# UC-521.net
KiCad netlist of a schematic drawn in Altium Designer
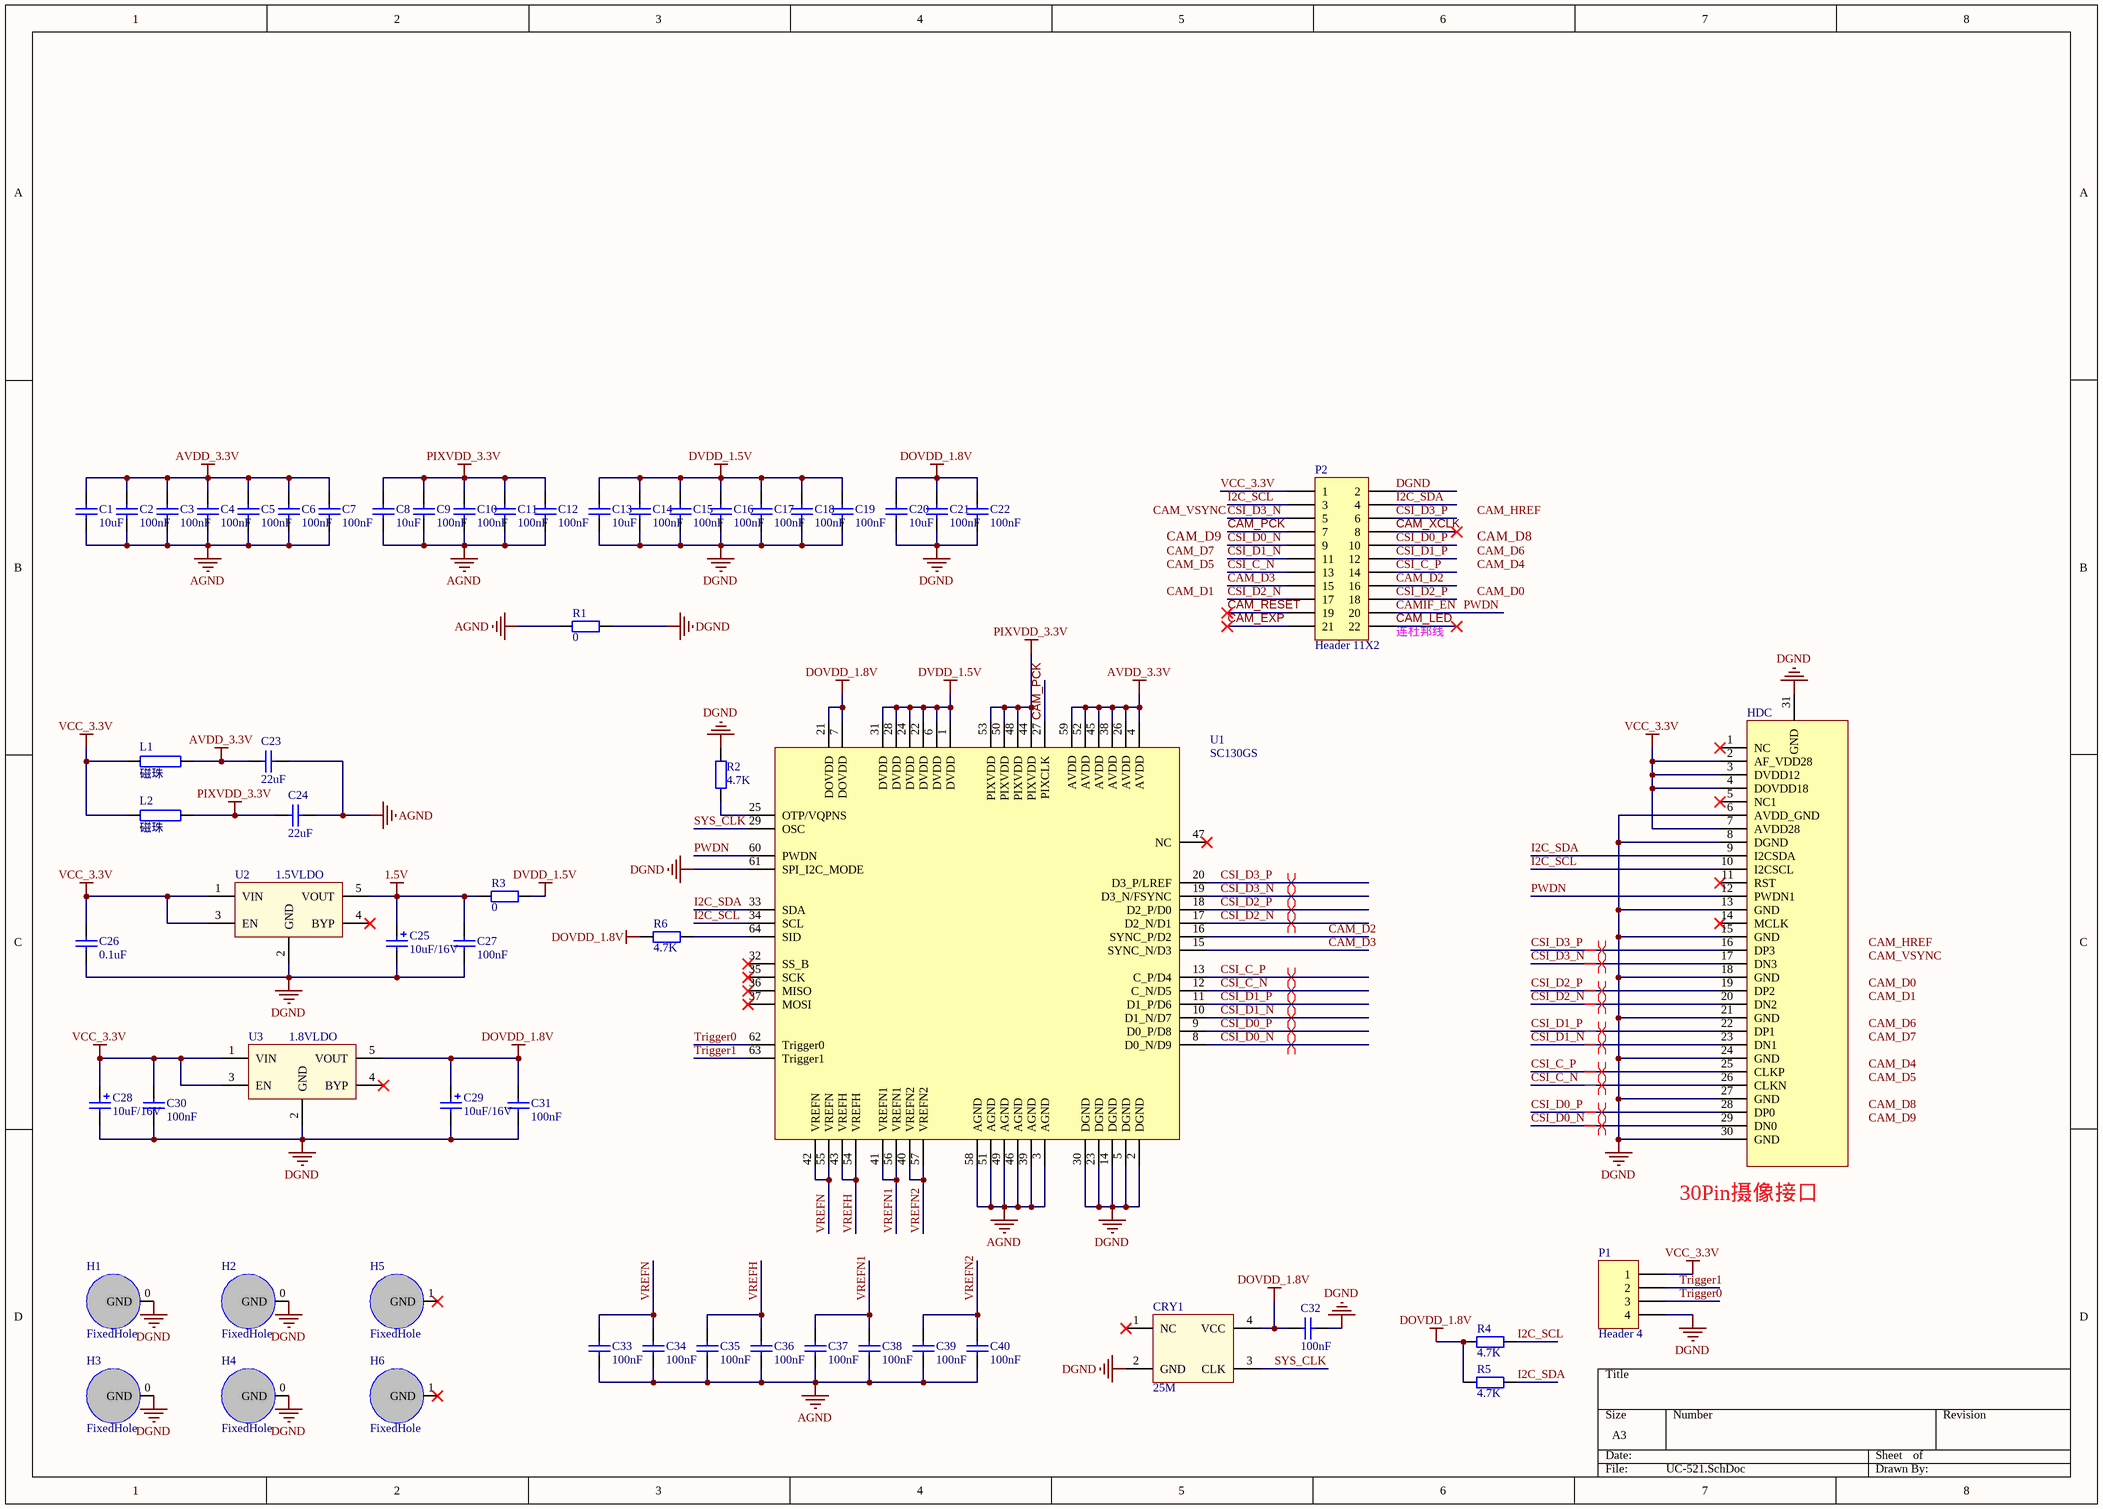
[diagram p0: UC-521.SchDoc]

(export (version "E")
  (design (tool "Eeschema 10.0.6"))
  (components
    (comp (ref "C1")
      (value "10uF")
      (footprint "C0603")
      (description "50V/8.2u/0805")
      (fields (field (name "PUBLISHER") "Altium Limited"))
      (libsource (lib "Miscellaneous Devices") (part "Cap"))
    )
    (comp (ref "C2")
      (value "100nF")
      (footprint "C0603")
      (description "50V/8.2u/0805")
      (fields (field (name "PUBLISHER") "Altium Limited"))
      (libsource (lib "Miscellaneous Devices") (part "Cap"))
    )
    (comp (ref "C3")
      (value "100nF")
      (footprint "C0603")
      (description "50V/8.2u/0805")
      (fields (field (name "PUBLISHER") "Altium Limited"))
      (libsource (lib "Miscellaneous Devices") (part "Cap"))
    )
    (comp (ref "C4")
      (value "100nF")
      (footprint "C0603")
      (description "50V/8.2u/0805")
      (fields (field (name "PUBLISHER") "Altium Limited"))
      (libsource (lib "Miscellaneous Devices") (part "Cap"))
    )
    (comp (ref "C5")
      (value "100nF")
      (footprint "C0603")
      (description "50V/8.2u/0805")
      (fields (field (name "PUBLISHER") "Altium Limited"))
      (libsource (lib "Miscellaneous Devices") (part "Cap"))
    )
    (comp (ref "C6")
      (value "100nF")
      (footprint "C0603")
      (description "50V/8.2u/0805")
      (fields (field (name "PUBLISHER") "Altium Limited"))
      (libsource (lib "Miscellaneous Devices") (part "Cap"))
    )
    (comp (ref "C7")
      (value "100nF")
      (footprint "C0603")
      (description "50V/8.2u/0805")
      (fields (field (name "PUBLISHER") "Altium Limited"))
      (libsource (lib "Miscellaneous Devices") (part "Cap"))
    )
    (comp (ref "C8")
      (value "10uF")
      (footprint "C0603")
      (description "50V/8.2u/0805")
      (fields (field (name "PUBLISHER") "Altium Limited"))
      (libsource (lib "Miscellaneous Devices") (part "Cap"))
    )
    (comp (ref "C9")
      (value "100nF")
      (footprint "C0603")
      (description "50V/8.2u/0805")
      (fields (field (name "PUBLISHER") "Altium Limited"))
      (libsource (lib "Miscellaneous Devices") (part "Cap"))
    )
    (comp (ref "C10")
      (value "100nF")
      (footprint "C0603")
      (description "50V/8.2u/0805")
      (fields (field (name "PUBLISHER") "Altium Limited"))
      (libsource (lib "Miscellaneous Devices") (part "Cap"))
    )
    (comp (ref "C11")
      (value "100nF")
      (footprint "C0603")
      (description "50V/8.2u/0805")
      (fields (field (name "PUBLISHER") "Altium Limited"))
      (libsource (lib "Miscellaneous Devices") (part "Cap"))
    )
    (comp (ref "C12")
      (value "100nF")
      (footprint "C0603")
      (description "50V/8.2u/0805")
      (fields (field (name "PUBLISHER") "Altium Limited"))
      (libsource (lib "Miscellaneous Devices") (part "Cap"))
    )
    (comp (ref "C13")
      (value "10uF")
      (footprint "C0603")
      (description "50V/8.2u/0805")
      (fields (field (name "PUBLISHER") "Altium Limited"))
      (libsource (lib "Miscellaneous Devices") (part "Cap"))
    )
    (comp (ref "C14")
      (value "100nF")
      (footprint "C0603")
      (description "50V/8.2u/0805")
      (fields (field (name "PUBLISHER") "Altium Limited"))
      (libsource (lib "Miscellaneous Devices") (part "Cap"))
    )
    (comp (ref "C15")
      (value "100nF")
      (footprint "C0603")
      (description "50V/8.2u/0805")
      (fields (field (name "PUBLISHER") "Altium Limited"))
      (libsource (lib "Miscellaneous Devices") (part "Cap"))
    )
    (comp (ref "C16")
      (value "100nF")
      (footprint "C0603")
      (description "50V/8.2u/0805")
      (fields (field (name "PUBLISHER") "Altium Limited"))
      (libsource (lib "Miscellaneous Devices") (part "Cap"))
    )
    (comp (ref "C17")
      (value "100nF")
      (footprint "C0603")
      (description "50V/8.2u/0805")
      (fields (field (name "PUBLISHER") "Altium Limited"))
      (libsource (lib "Miscellaneous Devices") (part "Cap"))
    )
    (comp (ref "C18")
      (value "100nF")
      (footprint "C0603")
      (description "50V/8.2u/0805")
      (fields (field (name "PUBLISHER") "Altium Limited"))
      (libsource (lib "Miscellaneous Devices") (part "Cap"))
    )
    (comp (ref "C19")
      (value "100nF")
      (footprint "C0603")
      (description "50V/8.2u/0805")
      (fields (field (name "PUBLISHER") "Altium Limited"))
      (libsource (lib "Miscellaneous Devices") (part "Cap"))
    )
    (comp (ref "C20")
      (value "10uF")
      (footprint "C0603")
      (description "50V/8.2u/0805")
      (fields (field (name "PUBLISHER") "Altium Limited"))
      (libsource (lib "Miscellaneous Devices") (part "Cap"))
    )
    (comp (ref "C21")
      (value "100nF")
      (footprint "C0603")
      (description "50V/8.2u/0805")
      (fields (field (name "PUBLISHER") "Altium Limited"))
      (libsource (lib "Miscellaneous Devices") (part "Cap"))
    )
    (comp (ref "C22")
      (value "100nF")
      (footprint "C0603")
      (description "50V/8.2u/0805")
      (fields (field (name "PUBLISHER") "Altium Limited"))
      (libsource (lib "Miscellaneous Devices") (part "Cap"))
    )
    (comp (ref "C23")
      (value "22uF")
      (footprint "C0603")
      (description "Capacitor")
      (fields (field (name "PUBLISHER") "Altium Limited"))
      (libsource (lib "Miscellaneous Devices") (part "Cap"))
    )
    (comp (ref "C24")
      (value "22uF")
      (footprint "C0603")
      (description "Capacitor")
      (fields (field (name "PUBLISHER") "Altium Limited"))
      (libsource (lib "Miscellaneous Devices") (part "Cap"))
    )
    (comp (ref "C25")
      (value "10uF/16V")
      (footprint "钽电容（A型）")
      (description "Polarized Capacitor (Axial)")
      (fields (field (name "PUBLISHER") "Altium Limited"))
      (libsource (lib "Miscellaneous Devices") (part "Cap Pol2"))
    )
    (comp (ref "C26")
      (value "0.1uF")
      (footprint "C0603")
      (description "Capacitor")
      (fields (field (name "PUBLISHER") "Altium Limited"))
      (libsource (lib "Miscellaneous Devices") (part "Cap"))
    )
    (comp (ref "C27")
      (value "100nF")
      (footprint "C0603")
      (description "Capacitor")
      (fields (field (name "PUBLISHER") "Altium Limited"))
      (libsource (lib "Miscellaneous Devices") (part "Cap"))
    )
    (comp (ref "C28")
      (value "10uF/16V")
      (footprint "钽电容（A型）")
      (description "Polarized Capacitor (Axial)")
      (fields (field (name "PUBLISHER") "Altium Limited"))
      (libsource (lib "Miscellaneous Devices") (part "Cap Pol2"))
    )
    (comp (ref "C29")
      (value "10uF/16V")
      (footprint "钽电容（A型）")
      (description "Polarized Capacitor (Axial)")
      (fields (field (name "PUBLISHER") "Altium Limited"))
      (libsource (lib "Miscellaneous Devices") (part "Cap Pol2"))
    )
    (comp (ref "C30")
      (value "100nF")
      (footprint "C0603")
      (description "Capacitor")
      (fields (field (name "PUBLISHER") "Altium Limited"))
      (libsource (lib "Miscellaneous Devices") (part "Cap"))
    )
    (comp (ref "C31")
      (value "100nF")
      (footprint "C0603")
      (description "Capacitor")
      (fields (field (name "PUBLISHER") "Altium Limited"))
      (libsource (lib "Miscellaneous Devices") (part "Cap"))
    )
    (comp (ref "C32")
      (value "100nF")
      (footprint "C0603")
      (description "50V/8.2u/0805")
      (fields (field (name "PUBLISHER") "Altium Limited"))
      (libsource (lib "Miscellaneous Devices") (part "Cap"))
    )
    (comp (ref "C33")
      (value "100nF")
      (footprint "C0603")
      (description "50V/8.2u/0805")
      (fields (field (name "PUBLISHER") "Altium Limited"))
      (libsource (lib "Miscellaneous Devices") (part "Cap"))
    )
    (comp (ref "C34")
      (value "100nF")
      (footprint "C0603")
      (description "50V/8.2u/0805")
      (fields (field (name "PUBLISHER") "Altium Limited"))
      (libsource (lib "Miscellaneous Devices") (part "Cap"))
    )
    (comp (ref "C35")
      (value "100nF")
      (footprint "C0603")
      (description "50V/8.2u/0805")
      (fields (field (name "PUBLISHER") "Altium Limited"))
      (libsource (lib "Miscellaneous Devices") (part "Cap"))
    )
    (comp (ref "C36")
      (value "100nF")
      (footprint "C0603")
      (description "50V/8.2u/0805")
      (fields (field (name "PUBLISHER") "Altium Limited"))
      (libsource (lib "Miscellaneous Devices") (part "Cap"))
    )
    (comp (ref "C37")
      (value "100nF")
      (footprint "C0603")
      (description "50V/8.2u/0805")
      (fields (field (name "PUBLISHER") "Altium Limited"))
      (libsource (lib "Miscellaneous Devices") (part "Cap"))
    )
    (comp (ref "C38")
      (value "100nF")
      (footprint "C0603")
      (description "50V/8.2u/0805")
      (fields (field (name "PUBLISHER") "Altium Limited"))
      (libsource (lib "Miscellaneous Devices") (part "Cap"))
    )
    (comp (ref "C39")
      (value "100nF")
      (footprint "C0603")
      (description "50V/8.2u/0805")
      (fields (field (name "PUBLISHER") "Altium Limited"))
      (libsource (lib "Miscellaneous Devices") (part "Cap"))
    )
    (comp (ref "C40")
      (value "100nF")
      (footprint "C0603")
      (description "50V/8.2u/0805")
      (fields (field (name "PUBLISHER") "Altium Limited"))
      (libsource (lib "Miscellaneous Devices") (part "Cap"))
    )
    (comp (ref "CRY1")
      (value "25M")
      (footprint "爱普生晶振3.2×2.5MM")
      (libsource (lib "MT9F002_V2.0") (part "24M"))
    )
    (comp (ref "H1")
      (value "FixedHole")
      (footprint "HOLE_M2")
      (libsource (lib "ITMS-02调试电缆转接板") (part "固定孔"))
    )
    (comp (ref "H2")
      (value "FixedHole")
      (footprint "HOLE_M2")
      (libsource (lib "ITMS-02调试电缆转接板") (part "固定孔"))
    )
    (comp (ref "H3")
      (value "FixedHole")
      (footprint "HOLE_M2")
      (libsource (lib "ITMS-02调试电缆转接板") (part "固定孔"))
    )
    (comp (ref "H4")
      (value "FixedHole")
      (footprint "HOLE_M2")
      (libsource (lib "ITMS-02调试电缆转接板") (part "固定孔"))
    )
    (comp (ref "H5") (value "FixedHole") (footprint "HOLE_M2") (libsource (lib "") (part "固定孔_1")))
    (comp (ref "H6") (value "FixedHole") (footprint "HOLE_M2") (libsource (lib "") (part "固定孔_1")))
    (comp (ref "HDC")
      (value "Component_1")
      (footprint "FH12-30S-0.5SH")
      (libsource (lib "Schlib1") (part "Component_1"))
    )
    (comp (ref "L1") (value "磁珠") (footprint "L0603") (libsource (lib "*") (part "RES")))
    (comp (ref "L2") (value "磁珠") (footprint "L0603") (libsource (lib "*") (part "RES")))
    (comp (ref "P1")
      (value "Header 4")
      (footprint "HDR1X4")
      (description "Header, 4-Pin")
      (fields (field (name "PUBLISHER") "Altium Limited"))
      (libsource (lib "Miscellaneous Connectors") (part "Header 4"))
    )
    (comp (ref "P2")
      (value "Header 11X2")
      (footprint "HDR2X11")
      (description "Header, 11-Pin, Dual row")
      (fields (field (name "PUBLISHER") "Altium Limited"))
      (libsource (lib "Miscellaneous Connectors") (part "Header 11X2"))
    )
    (comp (ref "R1")
      (value "0")
      (footprint "R0603")
      (description "Resistor")
      (fields (field (name "PUBLISHER") "Altium Limited"))
      (libsource (lib "DM642") (part "Res2"))
    )
    (comp (ref "R2")
      (value "4.7K")
      (footprint "R0603")
      (description "Resistor")
      (fields (field (name "PUBLISHER") "Altium Limited"))
      (libsource (lib "") (part "Res2_1"))
    )
    (comp (ref "R3")
      (value "0")
      (footprint "R0603")
      (description "Resistor")
      (fields (field (name "PUBLISHER") "Altium Limited"))
      (libsource (lib "DM642") (part "Res2"))
    )
    (comp (ref "R4")
      (value "4.7K")
      (footprint "R0603")
      (description "Resistor")
      (fields (field (name "PUBLISHER") "Altium Limited"))
      (libsource (lib "DM642") (part "Res2"))
    )
    (comp (ref "R5")
      (value "4.7K")
      (footprint "R0603")
      (description "Resistor")
      (fields (field (name "PUBLISHER") "Altium Limited"))
      (libsource (lib "DM642") (part "Res2"))
    )
    (comp (ref "R6")
      (value "4.7K")
      (footprint "R0603")
      (description "Resistor")
      (fields (field (name "PUBLISHER") "Altium Limited"))
      (libsource (lib "DM642") (part "Res2"))
    )
    (comp (ref "U1")
      (value "SC130GS")
      (footprint "LCC64-SC130GS")
      (libsource (lib "UC-5001") (part "SC130GS"))
    )
    (comp (ref "U2")
      (value "1.5VLDO")
      (footprint "SOT23-5")
      (libsource (lib "MT9F002_V2.0") (part "2.8VLDO"))
    )
    (comp (ref "U3")
      (value "1.8VLDO")
      (footprint "SOT23-5")
      (libsource (lib "MT9F002_V2.0") (part "2.8VLDO"))
    )
  )
  (nets
    (net (code "1") (name "/CAMIF_EN") (class "Default")
      (node (ref "HDC") (pin "12") (pinfunction "PWDN1_12") (pintype "passive"))
      (node (ref "P2") (pin "20") (pinfunction "20_20") (pintype "passive"))
      (node (ref "U1") (pin "60") (pinfunction "PWDN_60") (pintype "passive"))
    )
    (net (code "4") (name "/CAM_D2") (class "Default")
      (node (ref "P2") (pin "16") (pinfunction "16_16") (pintype "passive"))
      (node (ref "U1") (pin "16") (pinfunction "SYNC_P/D2_16") (pintype "passive"))
    )
    (net (code "5") (name "/CAM_D3") (class "Default")
      (node (ref "P2") (pin "15") (pinfunction "15_15") (pintype "passive"))
      (node (ref "U1") (pin "15") (pinfunction "SYNC_N/D3_15") (pintype "passive"))
    )
    (net (code "12") (name "/CAM_EXP") (class "Default")
      (node (ref "P2") (pin "21") (pinfunction "21_21") (pintype "passive+no_connect"))
    )
    (net (code "14") (name "/CAM_LED") (class "Default")
      (node (ref "P2") (pin "22") (pinfunction "22_22") (pintype "passive+no_connect"))
    )
    (net (code "15") (name "/CAM_PCK") (class "Default")
      (node (ref "P2") (pin "7") (pinfunction "7_7") (pintype "passive"))
      (node (ref "U1") (pin "27") (pinfunction "PIXCLK_27") (pintype "passive"))
    )
    (net (code "16") (name "/CAM_RESET") (class "Default")
      (node (ref "P2") (pin "19") (pinfunction "19_19") (pintype "passive+no_connect"))
    )
    (net (code "18") (name "/CAM_XCLK") (class "Default")
      (node (ref "P2") (pin "8") (pinfunction "8_8") (pintype "passive+no_connect"))
    )
    (net (code "19") (name "/CSI_C_N") (class "Default")
      (node (ref "HDC") (pin "26") (pinfunction "CLKN_26") (pintype "passive"))
      (node (ref "P2") (pin "13") (pinfunction "13_13") (pintype "passive"))
      (node (ref "U1") (pin "12") (pinfunction "C_N/D5_12") (pintype "passive"))
    )
    (net (code "20") (name "/CSI_C_P") (class "Default")
      (node (ref "HDC") (pin "25") (pinfunction "CLKP_25") (pintype "passive"))
      (node (ref "P2") (pin "14") (pinfunction "14_14") (pintype "passive"))
      (node (ref "U1") (pin "13") (pinfunction "C_P/D4_13") (pintype "passive"))
    )
    (net (code "21") (name "/CSI_D0_N") (class "Default")
      (node (ref "HDC") (pin "29") (pinfunction "DN0_29") (pintype "passive"))
      (node (ref "P2") (pin "9") (pinfunction "9_9") (pintype "passive"))
      (node (ref "U1") (pin "8") (pinfunction "D0_N/D9_8") (pintype "passive"))
    )
    (net (code "22") (name "/CSI_D0_P") (class "Default")
      (node (ref "HDC") (pin "28") (pinfunction "DP0_28") (pintype "passive"))
      (node (ref "P2") (pin "10") (pinfunction "10_10") (pintype "passive"))
      (node (ref "U1") (pin "9") (pinfunction "D0_P/D8_9") (pintype "passive"))
    )
    (net (code "23") (name "/CSI_D1_N") (class "Default")
      (node (ref "HDC") (pin "23") (pinfunction "DN1_23") (pintype "passive"))
      (node (ref "P2") (pin "11") (pinfunction "11_11") (pintype "passive"))
      (node (ref "U1") (pin "10") (pinfunction "D1_N/D7_10") (pintype "passive"))
    )
    (net (code "24") (name "/CSI_D1_P") (class "Default")
      (node (ref "HDC") (pin "22") (pinfunction "DP1_22") (pintype "passive"))
      (node (ref "P2") (pin "12") (pinfunction "12_12") (pintype "passive"))
      (node (ref "U1") (pin "11") (pinfunction "D1_P/D6_11") (pintype "passive"))
    )
    (net (code "25") (name "/CSI_D2_N") (class "Default")
      (node (ref "HDC") (pin "20") (pinfunction "DN2_20") (pintype "passive"))
      (node (ref "P2") (pin "17") (pinfunction "17_17") (pintype "passive"))
      (node (ref "U1") (pin "17") (pinfunction "D2_N/D1_17") (pintype "passive"))
    )
    (net (code "26") (name "/CSI_D2_P") (class "Default")
      (node (ref "HDC") (pin "19") (pinfunction "DP2_19") (pintype "passive"))
      (node (ref "P2") (pin "18") (pinfunction "18_18") (pintype "passive"))
      (node (ref "U1") (pin "18") (pinfunction "D2_P/D0_18") (pintype "passive"))
    )
    (net (code "27") (name "/CSI_D3_N") (class "Default")
      (node (ref "HDC") (pin "17") (pinfunction "DN3_17") (pintype "passive"))
      (node (ref "P2") (pin "5") (pinfunction "5_5") (pintype "passive"))
      (node (ref "U1") (pin "19") (pinfunction "D3_N/FSYNC_19") (pintype "passive"))
    )
    (net (code "28") (name "/CSI_D3_P") (class "Default")
      (node (ref "HDC") (pin "16") (pinfunction "DP3_16") (pintype "passive"))
      (node (ref "P2") (pin "6") (pinfunction "6_6") (pintype "passive"))
      (node (ref "U1") (pin "20") (pinfunction "D3_P/LREF_20") (pintype "passive"))
    )
    (net (code "29") (name "/I2C_SCL") (class "Default")
      (node (ref "HDC") (pin "10") (pinfunction "I2CSCL_10") (pintype "passive"))
      (node (ref "P2") (pin "3") (pinfunction "3_3") (pintype "passive"))
      (node (ref "R4") (pin "2") (pinfunction "2_2") (pintype "passive"))
      (node (ref "U1") (pin "34") (pinfunction "SCL_34") (pintype "passive"))
    )
    (net (code "30") (name "/I2C_SDA") (class "Default")
      (node (ref "HDC") (pin "9") (pinfunction "I2CSDA_9") (pintype "passive"))
      (node (ref "P2") (pin "4") (pinfunction "4_4") (pintype "passive"))
      (node (ref "R5") (pin "2") (pinfunction "2_2") (pintype "passive"))
      (node (ref "U1") (pin "33") (pinfunction "SDA_33") (pintype "passive"))
    )
    (net (code "31") (name "/SYS_CLK") (class "Default")
      (node (ref "CRY1") (pin "3") (pinfunction "CLK_3") (pintype "passive"))
      (node (ref "U1") (pin "29") (pinfunction "OSC_29") (pintype "passive"))
    )
    (net (code "32") (name "/Trigger0") (class "Default")
      (node (ref "P1") (pin "3") (pinfunction "3_3") (pintype "passive"))
      (node (ref "U1") (pin "62") (pinfunction "Trigger0_62") (pintype "passive"))
    )
    (net (code "33") (name "/Trigger1") (class "Default")
      (node (ref "P1") (pin "2") (pinfunction "2_2") (pintype "passive"))
      (node (ref "U1") (pin "63") (pinfunction "Trigger1_63") (pintype "passive"))
    )
    (net (code "34") (name "/VREFH") (class "Default")
      (node (ref "C35") (pin "1") (pinfunction "1_1") (pintype "passive"))
      (node (ref "C36") (pin "1") (pinfunction "1_1") (pintype "passive"))
      (node (ref "U1") (pin "43") (pinfunction "VREFH_43") (pintype "passive"))
      (node (ref "U1") (pin "54") (pinfunction "VREFH_54") (pintype "passive"))
    )
    (net (code "35") (name "/VREFN") (class "Default")
      (node (ref "C33") (pin "1") (pinfunction "1_1") (pintype "passive"))
      (node (ref "C34") (pin "1") (pinfunction "1_1") (pintype "passive"))
      (node (ref "U1") (pin "42") (pinfunction "VREFN_42") (pintype "passive"))
      (node (ref "U1") (pin "55") (pinfunction "VREFN_55") (pintype "passive"))
    )
    (net (code "36") (name "/VREFN1") (class "Default")
      (node (ref "C37") (pin "1") (pinfunction "1_1") (pintype "passive"))
      (node (ref "C38") (pin "1") (pinfunction "1_1") (pintype "passive"))
      (node (ref "U1") (pin "41") (pinfunction "VREFN1_41") (pintype "passive"))
      (node (ref "U1") (pin "56") (pinfunction "VREFN1_56") (pintype "passive"))
    )
    (net (code "37") (name "/VREFN2") (class "Default")
      (node (ref "C39") (pin "1") (pinfunction "1_1") (pintype "passive"))
      (node (ref "C40") (pin "1") (pinfunction "1_1") (pintype "passive"))
      (node (ref "U1") (pin "40") (pinfunction "VREFN2_40") (pintype "passive"))
      (node (ref "U1") (pin "57") (pinfunction "VREFN2_57") (pintype "passive"))
    )
    (net (code "38") (name "1.5V") (class "Default")
      (node (ref "C25") (pin "1") (pinfunction "1_1") (pintype "passive"))
      (node (ref "C27") (pin "1") (pinfunction "1_1") (pintype "passive"))
      (node (ref "R3") (pin "1") (pinfunction "1_1") (pintype "passive"))
      (node (ref "U2") (pin "5") (pinfunction "VOUT_5") (pintype "passive"))
    )
    (net (code "39") (name "AGND") (class "Default")
      (node (ref "C1") (pin "2") (pinfunction "2_2") (pintype "passive"))
      (node (ref "C10") (pin "2") (pinfunction "2_2") (pintype "passive"))
      (node (ref "C11") (pin "2") (pinfunction "2_2") (pintype "passive"))
      (node (ref "C12") (pin "2") (pinfunction "2_2") (pintype "passive"))
      (node (ref "C2") (pin "2") (pinfunction "2_2") (pintype "passive"))
      (node (ref "C23") (pin "1") (pinfunction "1_1") (pintype "passive"))
      (node (ref "C24") (pin "1") (pinfunction "1_1") (pintype "passive"))
      (node (ref "C3") (pin "2") (pinfunction "2_2") (pintype "passive"))
      (node (ref "C33") (pin "2") (pinfunction "2_2") (pintype "passive"))
      (node (ref "C34") (pin "2") (pinfunction "2_2") (pintype "passive"))
      (node (ref "C35") (pin "2") (pinfunction "2_2") (pintype "passive"))
      (node (ref "C36") (pin "2") (pinfunction "2_2") (pintype "passive"))
      (node (ref "C37") (pin "2") (pinfunction "2_2") (pintype "passive"))
      (node (ref "C38") (pin "2") (pinfunction "2_2") (pintype "passive"))
      (node (ref "C39") (pin "2") (pinfunction "2_2") (pintype "passive"))
      (node (ref "C4") (pin "2") (pinfunction "2_2") (pintype "passive"))
      (node (ref "C40") (pin "2") (pinfunction "2_2") (pintype "passive"))
      (node (ref "C5") (pin "2") (pinfunction "2_2") (pintype "passive"))
      (node (ref "C6") (pin "2") (pinfunction "2_2") (pintype "passive"))
      (node (ref "C7") (pin "2") (pinfunction "2_2") (pintype "passive"))
      (node (ref "C8") (pin "2") (pinfunction "2_2") (pintype "passive"))
      (node (ref "C9") (pin "2") (pinfunction "2_2") (pintype "passive"))
      (node (ref "R1") (pin "1") (pinfunction "1_1") (pintype "passive"))
      (node (ref "U1") (pin "3") (pinfunction "AGND_3") (pintype "passive"))
      (node (ref "U1") (pin "39") (pinfunction "AGND_39") (pintype "passive"))
      (node (ref "U1") (pin "46") (pinfunction "AGND_46") (pintype "passive"))
      (node (ref "U1") (pin "49") (pinfunction "AGND_49") (pintype "passive"))
      (node (ref "U1") (pin "51") (pinfunction "AGND_51") (pintype "passive"))
      (node (ref "U1") (pin "58") (pinfunction "AGND_58") (pintype "passive"))
    )
    (net (code "40") (name "AVDD_3.3V") (class "Default")
      (node (ref "C1") (pin "1") (pinfunction "1_1") (pintype "passive"))
      (node (ref "C2") (pin "1") (pinfunction "1_1") (pintype "passive"))
      (node (ref "C23") (pin "2") (pinfunction "2_2") (pintype "passive"))
      (node (ref "C3") (pin "1") (pinfunction "1_1") (pintype "passive"))
      (node (ref "C4") (pin "1") (pinfunction "1_1") (pintype "passive"))
      (node (ref "C5") (pin "1") (pinfunction "1_1") (pintype "passive"))
      (node (ref "C6") (pin "1") (pinfunction "1_1") (pintype "passive"))
      (node (ref "C7") (pin "1") (pinfunction "1_1") (pintype "passive"))
      (node (ref "L1") (pin "2") (pinfunction "2_2") (pintype "passive"))
      (node (ref "U1") (pin "26") (pinfunction "AVDD_26") (pintype "passive"))
      (node (ref "U1") (pin "38") (pinfunction "AVDD_38") (pintype "passive"))
      (node (ref "U1") (pin "4") (pinfunction "AVDD_4") (pintype "passive"))
      (node (ref "U1") (pin "45") (pinfunction "AVDD_45") (pintype "passive"))
      (node (ref "U1") (pin "52") (pinfunction "AVDD_52") (pintype "passive"))
      (node (ref "U1") (pin "59") (pinfunction "AVDD_59") (pintype "passive"))
    )
    (net (code "41") (name "DGND") (class "Default")
      (node (ref "C13") (pin "2") (pinfunction "2_2") (pintype "passive"))
      (node (ref "C14") (pin "2") (pinfunction "2_2") (pintype "passive"))
      (node (ref "C15") (pin "2") (pinfunction "2_2") (pintype "passive"))
      (node (ref "C16") (pin "2") (pinfunction "2_2") (pintype "passive"))
      (node (ref "C17") (pin "2") (pinfunction "2_2") (pintype "passive"))
      (node (ref "C18") (pin "2") (pinfunction "2_2") (pintype "passive"))
      (node (ref "C19") (pin "2") (pinfunction "2_2") (pintype "passive"))
      (node (ref "C20") (pin "2") (pinfunction "2_2") (pintype "passive"))
      (node (ref "C21") (pin "2") (pinfunction "2_2") (pintype "passive"))
      (node (ref "C22") (pin "2") (pinfunction "2_2") (pintype "passive"))
      (node (ref "C25") (pin "2") (pinfunction "2_2") (pintype "passive"))
      (node (ref "C26") (pin "2") (pinfunction "2_2") (pintype "passive"))
      (node (ref "C27") (pin "2") (pinfunction "2_2") (pintype "passive"))
      (node (ref "C28") (pin "2") (pinfunction "2_2") (pintype "passive"))
      (node (ref "C29") (pin "2") (pinfunction "2_2") (pintype "passive"))
      (node (ref "C30") (pin "2") (pinfunction "2_2") (pintype "passive"))
      (node (ref "C31") (pin "2") (pinfunction "2_2") (pintype "passive"))
      (node (ref "C32") (pin "2") (pinfunction "2_2") (pintype "passive"))
      (node (ref "CRY1") (pin "2") (pinfunction "GND_2") (pintype "passive"))
      (node (ref "H1") (pin "0") (pinfunction "GND_0") (pintype "passive"))
      (node (ref "H2") (pin "0") (pinfunction "GND_0") (pintype "passive"))
      (node (ref "H3") (pin "0") (pinfunction "GND_0") (pintype "passive"))
      (node (ref "H4") (pin "0") (pinfunction "GND_0") (pintype "passive"))
      (node (ref "HDC") (pin "13") (pinfunction "GND_13") (pintype "passive"))
      (node (ref "HDC") (pin "15") (pinfunction "GND_15") (pintype "passive"))
      (node (ref "HDC") (pin "18") (pinfunction "GND_18") (pintype "passive"))
      (node (ref "HDC") (pin "21") (pinfunction "GND_21") (pintype "passive"))
      (node (ref "HDC") (pin "24") (pinfunction "GND_24") (pintype "passive"))
      (node (ref "HDC") (pin "27") (pinfunction "GND_27") (pintype "passive"))
      (node (ref "HDC") (pin "30") (pinfunction "GND_30") (pintype "passive"))
      (node (ref "HDC") (pin "31") (pinfunction "GND_31") (pintype "passive"))
      (node (ref "HDC") (pin "6") (pinfunction "AVDD_GND_6") (pintype "passive"))
      (node (ref "HDC") (pin "8") (pinfunction "DGND_8") (pintype "passive"))
      (node (ref "P1") (pin "4") (pinfunction "4_4") (pintype "passive"))
      (node (ref "P2") (pin "2") (pinfunction "2_2") (pintype "passive"))
      (node (ref "R1") (pin "2") (pinfunction "2_2") (pintype "passive"))
      (node (ref "R2") (pin "1") (pinfunction "1_1") (pintype "passive"))
      (node (ref "U1") (pin "14") (pinfunction "DGND_14") (pintype "passive"))
      (node (ref "U1") (pin "2") (pinfunction "DGND_2") (pintype "passive"))
      (node (ref "U1") (pin "23") (pinfunction "DGND_23") (pintype "passive"))
      (node (ref "U1") (pin "30") (pinfunction "DGND_30") (pintype "passive"))
      (node (ref "U1") (pin "5") (pinfunction "DGND_5") (pintype "passive"))
      (node (ref "U1") (pin "61") (pinfunction "SPI_I2C_MODE_61") (pintype "passive"))
      (node (ref "U2") (pin "2") (pinfunction "GND_2") (pintype "passive"))
      (node (ref "U3") (pin "2") (pinfunction "GND_2") (pintype "passive"))
    )
    (net (code "42") (name "DOVDD_1.8V") (class "Default")
      (node (ref "C20") (pin "1") (pinfunction "1_1") (pintype "passive"))
      (node (ref "C21") (pin "1") (pinfunction "1_1") (pintype "passive"))
      (node (ref "C22") (pin "1") (pinfunction "1_1") (pintype "passive"))
      (node (ref "C29") (pin "1") (pinfunction "1_1") (pintype "passive"))
      (node (ref "C31") (pin "1") (pinfunction "1_1") (pintype "passive"))
      (node (ref "C32") (pin "1") (pinfunction "1_1") (pintype "passive"))
      (node (ref "CRY1") (pin "4") (pinfunction "VCC_4") (pintype "passive"))
      (node (ref "R4") (pin "1") (pinfunction "1_1") (pintype "passive"))
      (node (ref "R5") (pin "1") (pinfunction "1_1") (pintype "passive"))
      (node (ref "R6") (pin "1") (pinfunction "1_1") (pintype "passive"))
      (node (ref "U1") (pin "21") (pinfunction "DOVDD_21") (pintype "passive"))
      (node (ref "U1") (pin "7") (pinfunction "DOVDD_7") (pintype "passive"))
      (node (ref "U3") (pin "5") (pinfunction "VOUT_5") (pintype "passive"))
    )
    (net (code "43") (name "DVDD_1.5V") (class "Default")
      (node (ref "C13") (pin "1") (pinfunction "1_1") (pintype "passive"))
      (node (ref "C14") (pin "1") (pinfunction "1_1") (pintype "passive"))
      (node (ref "C15") (pin "1") (pinfunction "1_1") (pintype "passive"))
      (node (ref "C16") (pin "1") (pinfunction "1_1") (pintype "passive"))
      (node (ref "C17") (pin "1") (pinfunction "1_1") (pintype "passive"))
      (node (ref "C18") (pin "1") (pinfunction "1_1") (pintype "passive"))
      (node (ref "C19") (pin "1") (pinfunction "1_1") (pintype "passive"))
      (node (ref "R3") (pin "2") (pinfunction "2_2") (pintype "passive"))
      (node (ref "U1") (pin "1") (pinfunction "DVDD_1") (pintype "passive"))
      (node (ref "U1") (pin "22") (pinfunction "DVDD_22") (pintype "passive"))
      (node (ref "U1") (pin "24") (pinfunction "DVDD_24") (pintype "passive"))
      (node (ref "U1") (pin "28") (pinfunction "DVDD_28") (pintype "passive"))
      (node (ref "U1") (pin "31") (pinfunction "DVDD_31") (pintype "passive"))
      (node (ref "U1") (pin "6") (pinfunction "DVDD_6") (pintype "passive"))
    )
    (net (code "44") (name "Net-(U1-OTP{slash}VQPNS)") (class "Default")
      (node (ref "R2") (pin "2") (pinfunction "2_2") (pintype "passive"))
      (node (ref "U1") (pin "25") (pinfunction "OTP/VQPNS_25") (pintype "passive"))
    )
    (net (code "45") (name "Net-(U1-SID)") (class "Default")
      (node (ref "R6") (pin "2") (pinfunction "2_2") (pintype "passive"))
      (node (ref "U1") (pin "64") (pinfunction "SID_64") (pintype "passive"))
    )
    (net (code "46") (name "PIXVDD_3.3V") (class "Default")
      (node (ref "C10") (pin "1") (pinfunction "1_1") (pintype "passive"))
      (node (ref "C11") (pin "1") (pinfunction "1_1") (pintype "passive"))
      (node (ref "C12") (pin "1") (pinfunction "1_1") (pintype "passive"))
      (node (ref "C24") (pin "2") (pinfunction "2_2") (pintype "passive"))
      (node (ref "C8") (pin "1") (pinfunction "1_1") (pintype "passive"))
      (node (ref "C9") (pin "1") (pinfunction "1_1") (pintype "passive"))
      (node (ref "L2") (pin "1") (pinfunction "1_1") (pintype "passive"))
      (node (ref "U1") (pin "44") (pinfunction "PIXVDD_44") (pintype "passive"))
      (node (ref "U1") (pin "48") (pinfunction "PIXVDD_48") (pintype "passive"))
      (node (ref "U1") (pin "50") (pinfunction "PIXVDD_50") (pintype "passive"))
      (node (ref "U1") (pin "53") (pinfunction "PIXVDD_53") (pintype "passive"))
    )
    (net (code "47") (name "VCC_3.3V") (class "Default")
      (node (ref "C26") (pin "1") (pinfunction "1_1") (pintype "passive"))
      (node (ref "C28") (pin "1") (pinfunction "1_1") (pintype "passive"))
      (node (ref "C30") (pin "1") (pinfunction "1_1") (pintype "passive"))
      (node (ref "HDC") (pin "2") (pinfunction "AF_VDD28_2") (pintype "passive"))
      (node (ref "HDC") (pin "3") (pinfunction "DVDD12_3") (pintype "passive"))
      (node (ref "HDC") (pin "4") (pinfunction "DOVDD18_4") (pintype "passive"))
      (node (ref "HDC") (pin "7") (pinfunction "AVDD28_7") (pintype "passive"))
      (node (ref "L1") (pin "1") (pinfunction "1_1") (pintype "passive"))
      (node (ref "L2") (pin "2") (pinfunction "2_2") (pintype "passive"))
      (node (ref "P1") (pin "1") (pinfunction "1_1") (pintype "passive"))
      (node (ref "P2") (pin "1") (pinfunction "1_1") (pintype "passive"))
      (node (ref "U2") (pin "1") (pinfunction "VIN_1") (pintype "passive"))
      (node (ref "U2") (pin "3") (pinfunction "EN_3") (pintype "passive"))
      (node (ref "U3") (pin "1") (pinfunction "VIN_1") (pintype "passive"))
      (node (ref "U3") (pin "3") (pinfunction "EN_3") (pintype "passive"))
    )
    (net (code "48") (name "unconnected-(CRY1-NC-Pad1)") (class "Default")
      (node (ref "CRY1") (pin "1") (pinfunction "NC_1") (pintype "passive+no_connect"))
    )
    (net (code "49") (name "unconnected-(H5-GND-Pad1)") (class "Default")
      (node (ref "H5") (pin "1") (pinfunction "GND_1") (pintype "passive+no_connect"))
    )
    (net (code "50") (name "unconnected-(H6-GND-Pad1)") (class "Default")
      (node (ref "H6") (pin "1") (pinfunction "GND_1") (pintype "passive+no_connect"))
    )
    (net (code "51") (name "unconnected-(HDC-MCLK-Pad14)") (class "Default")
      (node (ref "HDC") (pin "14") (pinfunction "MCLK_14") (pintype "passive+no_connect"))
    )
    (net (code "52") (name "unconnected-(HDC-NC-Pad1)") (class "Default")
      (node (ref "HDC") (pin "1") (pinfunction "NC_1") (pintype "passive+no_connect"))
    )
    (net (code "53") (name "unconnected-(HDC-NC1-Pad5)") (class "Default")
      (node (ref "HDC") (pin "5") (pinfunction "NC1_5") (pintype "passive+no_connect"))
    )
    (net (code "54") (name "unconnected-(HDC-RST-Pad11)") (class "Default")
      (node (ref "HDC") (pin "11") (pinfunction "RST_11") (pintype "passive+no_connect"))
    )
    (net (code "55") (name "unconnected-(U1-MISO-Pad36)") (class "Default")
      (node (ref "U1") (pin "36") (pinfunction "MISO_36") (pintype "passive+no_connect"))
    )
    (net (code "56") (name "unconnected-(U1-MOSI-Pad37)") (class "Default")
      (node (ref "U1") (pin "37") (pinfunction "MOSI_37") (pintype "passive+no_connect"))
    )
    (net (code "57") (name "unconnected-(U1-NC-Pad47)") (class "Default")
      (node (ref "U1") (pin "47") (pinfunction "NC_47") (pintype "passive+no_connect"))
    )
    (net (code "58") (name "unconnected-(U1-SCK-Pad35)") (class "Default")
      (node (ref "U1") (pin "35") (pinfunction "SCK_35") (pintype "passive+no_connect"))
    )
    (net (code "59") (name "unconnected-(U1-SS_B-Pad32)") (class "Default")
      (node (ref "U1") (pin "32") (pinfunction "SS_B_32") (pintype "passive+no_connect"))
    )
    (net (code "60") (name "unconnected-(U2-BYP-Pad4)") (class "Default")
      (node (ref "U2") (pin "4") (pinfunction "BYP_4") (pintype "passive+no_connect"))
    )
    (net (code "61") (name "unconnected-(U3-BYP-Pad4)") (class "Default")
      (node (ref "U3") (pin "4") (pinfunction "BYP_4") (pintype "passive+no_connect"))
    )
  )
)
